# GDOv5_Board.net
KiCad netlist of a schematic drawn in EAGLE
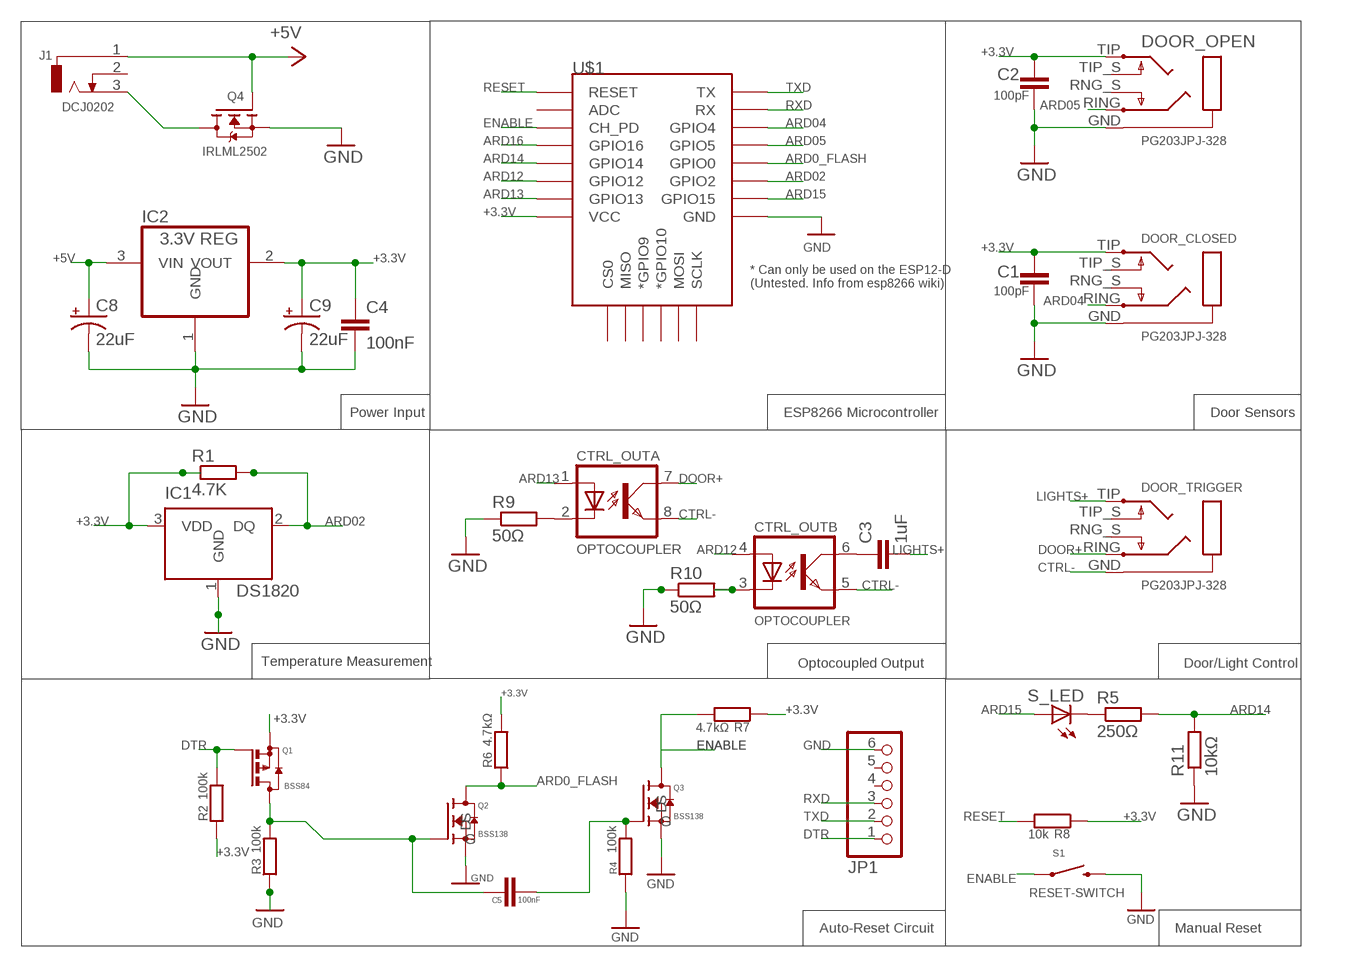
[diagram p0: schematic, sheet 1]

(export (version "E")
  (design (tool "Eeschema 10.0.6"))
  (components
    (comp (ref "C1")
      (value "100pF")
      (footprint "eagle-import:C1206")
      (libsource (lib "eagle-import") (part "C-EUC1206"))
    )
    (comp (ref "C2")
      (value "100pF")
      (footprint "eagle-import:C1206")
      (libsource (lib "eagle-import") (part "C-EUC1206"))
    )
    (comp (ref "C3")
      (value "1uF")
      (footprint "eagle-import:1206")
      (libsource (lib "eagle-import") (part "CAP1206"))
    )
    (comp (ref "C4")
      (value "100nF")
      (footprint "eagle-import:C1206")
      (libsource (lib "eagle-import") (part "C-EUC1206"))
    )
    (comp (ref "C5")
      (value "100nF")
      (footprint "eagle-import:C1206")
      (libsource (lib "eagle-import") (part "C-EUC1206"))
    )
    (comp (ref "C8")
      (value "22uF")
      (footprint "eagle-import:EIA3216")
      (libsource (lib "eagle-import") (part "10UF-TANT"))
    )
    (comp (ref "C9")
      (value "22uF")
      (footprint "eagle-import:EIA3216")
      (libsource (lib "eagle-import") (part "10UF-TANT"))
    )
    (comp (ref "CTRL_OUT")
      (value "OPTOCOUPLER")
      (footprint "eagle-import:DIL08")
      (libsource (lib "eagle-import") (part "ILD2"))
    )
    (comp (ref "DOOR_CLOSED")
      (value "PG203JPJ-328")
      (footprint "eagle-import:PG203J")
      (libsource (lib "eagle-import") (part "PG203JPJ-328"))
    )
    (comp (ref "DOOR_OPEN")
      (value "PG203JPJ-328")
      (footprint "eagle-import:PG203J")
      (libsource (lib "eagle-import") (part "PG203JPJ-328"))
    )
    (comp (ref "DOOR_TRIGGER")
      (value "PG203JPJ-328")
      (footprint "eagle-import:PG203J")
      (libsource (lib "eagle-import") (part "PG203JPJ-328"))
    )
    (comp (ref "IC1")
      (value "DS1820")
      (footprint "eagle-import:TO-92")
      (libsource (lib "eagle-import") (part "DS1820"))
    )
    (comp (ref "IC2")
      (value "3.3V REG")
      (footprint "eagle-import:SOT223")
      (fields (field (name "MPN") "REG1117"))
      (libsource (lib "eagle-import") (part "REG1117"))
    )
    (comp (ref "J1")
      (value "DCJ0202")
      (footprint "eagle-import:DCJ0202")
      (libsource (lib "eagle-import") (part "DCJ0202"))
    )
    (comp (ref "JP1")
      (value "PINHD-1X6")
      (footprint "eagle-import:1X06")
      (libsource (lib "eagle-import") (part "PINHD-1X6"))
    )
    (comp (ref "Q1")
      (value "BSS84")
      (footprint "eagle-import:SOT23")
      (libsource (lib "eagle-import") (part "BSS84"))
    )
    (comp (ref "Q2")
      (value "BSS138")
      (footprint "eagle-import:BSS138")
      (libsource (lib "eagle-import") (part "BSS138"))
    )
    (comp (ref "Q3")
      (value "BSS138")
      (footprint "eagle-import:BSS138")
      (libsource (lib "eagle-import") (part "BSS138"))
    )
    (comp (ref "Q4")
      (value "IRLML2502")
      (footprint "eagle-import:SOT23")
      (fields (field (name "MF") "Fairchild") (field (name "MPN") "BSS138"))
      (libsource (lib "eagle-import") (part "bss138_10_BSS138"))
    )
    (comp (ref "R1")
      (value "4.7K")
      (footprint "eagle-import:M3216")
      (libsource (lib "eagle-import") (part "R-EU_M3216"))
    )
    (comp (ref "R2")
      (value "100k")
      (footprint "eagle-import:M3216")
      (libsource (lib "eagle-import") (part "R-EU_M3216"))
    )
    (comp (ref "R3")
      (value "100k")
      (footprint "eagle-import:M3216")
      (libsource (lib "eagle-import") (part "R-EU_M3216"))
    )
    (comp (ref "R4")
      (value "100k")
      (footprint "eagle-import:M3216")
      (libsource (lib "eagle-import") (part "R-EU_M3216"))
    )
    (comp (ref "R5")
      (value "250Ω")
      (footprint "eagle-import:M3216")
      (libsource (lib "eagle-import") (part "R-EU_M3216"))
    )
    (comp (ref "R6")
      (value "4.7kΩ")
      (footprint "eagle-import:M3216")
      (libsource (lib "eagle-import") (part "R-EU_M3216"))
    )
    (comp (ref "R7")
      (value "4.7kΩ")
      (footprint "eagle-import:M3216")
      (libsource (lib "eagle-import") (part "R-EU_M3216"))
    )
    (comp (ref "R8")
      (value "10k")
      (footprint "eagle-import:M3216")
      (libsource (lib "eagle-import") (part "R-EU_M3216"))
    )
    (comp (ref "R9")
      (value "50Ω")
      (footprint "eagle-import:M3216")
      (libsource (lib "eagle-import") (part "R-EU_M3216"))
    )
    (comp (ref "R10")
      (value "50Ω")
      (footprint "eagle-import:M3216")
      (libsource (lib "eagle-import") (part "R-EU_M3216"))
    )
    (comp (ref "R11")
      (value "10kΩ")
      (footprint "eagle-import:M3216")
      (libsource (lib "eagle-import") (part "R-EU_M3216"))
    )
    (comp (ref "S1")
      (value "RESET-SWITCH")
      (footprint "eagle-import:TACTILE-SWITCH-1101NE")
      (libsource (lib "eagle-import") (part "SWITCH-MOMENTARY-2-SMD-1101NE"))
    )
    (comp (ref "S_LED")
      (value "LED5MM")
      (footprint "eagle-import:LED5MM")
      (libsource (lib "eagle-import") (part "LED5MM"))
    )
    (comp (ref "U$1")
      (value "ESP12ESMD")
      (footprint "eagle-import:ESP12E-SMD")
      (libsource (lib "eagle-import") (part "ESP12ESMD"))
    )
  )
  (nets
    (net (code "1") (name "+5V") (class "Default")
      (node (ref "C8") (pin "A") (pinfunction "+_A") (pintype "passive"))
      (node (ref "IC2") (pin "3") (pinfunction "VIN_3") (pintype "input"))
      (node (ref "J1") (pin "1") (pinfunction "1_1") (pintype "passive"))
      (node (ref "Q4") (pin "1") (pinfunction "G_1") (pintype "passive"))
    )
    (net (code "2") (name "/+3.3V") (class "Default")
      (node (ref "C1") (pin "1") (pinfunction "1_1") (pintype "passive"))
      (node (ref "C2") (pin "1") (pinfunction "1_1") (pintype "passive"))
      (node (ref "C4") (pin "1") (pinfunction "1_1") (pintype "passive"))
      (node (ref "C9") (pin "A") (pinfunction "+_A") (pintype "passive"))
      (node (ref "DOOR_CLOSED") (pin "TIP") (pinfunction "5_TIP") (pintype "passive"))
      (node (ref "DOOR_OPEN") (pin "TIP") (pinfunction "5_TIP") (pintype "passive"))
      (node (ref "IC1") (pin "3") (pinfunction "VDD_3") (pintype "input"))
      (node (ref "IC2") (pin "2") (pinfunction "VOUT_2") (pintype "output"))
      (node (ref "Q1") (pin "2") (pinfunction "S_2") (pintype "passive"))
      (node (ref "R1") (pin "1") (pinfunction "1_1") (pintype "passive"))
      (node (ref "R2") (pin "1") (pinfunction "1_1") (pintype "passive"))
      (node (ref "R6") (pin "2") (pinfunction "2_2") (pintype "passive"))
      (node (ref "R7") (pin "1") (pinfunction "1_1") (pintype "passive"))
      (node (ref "R8") (pin "1") (pinfunction "1_1") (pintype "passive"))
      (node (ref "U$1") (pin "VCC") (pinfunction "VCC_VCC") (pintype "bidirectional"))
    )
    (net (code "3") (name "/ARD0_FLASH") (class "Default")
      (node (ref "Q2") (pin "D") (pinfunction "D_D") (pintype "passive"))
      (node (ref "R6") (pin "1") (pinfunction "1_1") (pintype "passive"))
      (node (ref "U$1") (pin "GPIO0") (pinfunction "GPIO0_GPIO0") (pintype "bidirectional"))
    )
    (net (code "4") (name "/ARD02") (class "Default")
      (node (ref "IC1") (pin "2") (pinfunction "DQ_2") (pintype "output"))
      (node (ref "R1") (pin "2") (pinfunction "2_2") (pintype "passive"))
      (node (ref "U$1") (pin "GPIO2") (pinfunction "GPIO2_GPIO2") (pintype "bidirectional"))
    )
    (net (code "5") (name "/ARD04") (class "Default")
      (node (ref "DOOR_CLOSED") (pin "RING") (pinfunction "2_RING") (pintype "passive"))
      (node (ref "U$1") (pin "GPIO4") (pinfunction "GPIO4_GPIO4") (pintype "bidirectional"))
    )
    (net (code "6") (name "/ARD05") (class "Default")
      (node (ref "DOOR_OPEN") (pin "RING") (pinfunction "2_RING") (pintype "passive"))
      (node (ref "U$1") (pin "GPIO5") (pinfunction "GPIO5_GPIO5") (pintype "bidirectional"))
    )
    (net (code "7") (name "/ARD12") (class "Default")
      (node (ref "CTRL_OUT") (pin "4") (pinfunction "A_4") (pintype "passive"))
      (node (ref "U$1") (pin "GPIO12") (pinfunction "GPIO12_GPIO12") (pintype "bidirectional"))
    )
    (net (code "8") (name "/ARD13") (class "Default")
      (node (ref "CTRL_OUT") (pin "1") (pinfunction "A_1") (pintype "passive"))
      (node (ref "U$1") (pin "GPIO13") (pinfunction "GPIO13_GPIO13") (pintype "bidirectional"))
    )
    (net (code "9") (name "/ARD14") (class "Default")
      (node (ref "R11") (pin "2") (pinfunction "2_2") (pintype "passive"))
      (node (ref "R5") (pin "2") (pinfunction "2_2") (pintype "passive"))
      (node (ref "U$1") (pin "GPIO14") (pinfunction "GPIO14_GPIO14") (pintype "bidirectional"))
    )
    (net (code "10") (name "/ARD15") (class "Default")
      (node (ref "S_LED") (pin "A") (pinfunction "A_A") (pintype "passive"))
      (node (ref "U$1") (pin "GPIO15") (pinfunction "GPIO15_GPIO15") (pintype "bidirectional"))
    )
    (net (code "11") (name "/ARD16") (class "Default")
      (node (ref "U$1") (pin "GPIO16") (pinfunction "GPIO16_GPIO16") (pintype "bidirectional"))
    )
    (net (code "12") (name "/CTRL-") (class "Default")
      (node (ref "CTRL_OUT") (pin "5") (pinfunction "EMIT_5") (pintype "passive"))
      (node (ref "CTRL_OUT") (pin "8") (pinfunction "EMIT_8") (pintype "passive"))
      (node (ref "DOOR_TRIGGER") (pin "GND") (pinfunction "1_GND") (pintype "passive"))
    )
    (net (code "13") (name "/DOOR+") (class "Default")
      (node (ref "CTRL_OUT") (pin "7") (pinfunction "COL_7") (pintype "passive"))
      (node (ref "DOOR_TRIGGER") (pin "RING") (pinfunction "2_RING") (pintype "passive"))
    )
    (net (code "14") (name "/DTR") (class "Default")
      (node (ref "JP1") (pin "1") (pinfunction "1_1") (pintype "passive"))
      (node (ref "Q1") (pin "1") (pinfunction "G_1") (pintype "passive"))
      (node (ref "R2") (pin "2") (pinfunction "2_2") (pintype "passive"))
    )
    (net (code "15") (name "/ENABLE") (class "Default")
      (node (ref "Q3") (pin "D") (pinfunction "D_D") (pintype "passive"))
      (node (ref "R7") (pin "2") (pinfunction "2_2") (pintype "passive"))
      (node (ref "S1") (pin "P$1") (pinfunction "1_P$1") (pintype "passive"))
      (node (ref "U$1") (pin "CH_PD") (pinfunction "CH_PD_CH_PD") (pintype "bidirectional"))
    )
    (net (code "16") (name "/LIGHTS+") (class "Default")
      (node (ref "C3") (pin "2") (pinfunction "2_2") (pintype "passive"))
      (node (ref "DOOR_TRIGGER") (pin "TIP") (pinfunction "5_TIP") (pintype "passive"))
    )
    (net (code "17") (name "/RESET") (class "Default")
      (node (ref "R8") (pin "2") (pinfunction "2_2") (pintype "passive"))
      (node (ref "U$1") (pin "RESET") (pinfunction "RESET_RESET") (pintype "bidirectional"))
    )
    (net (code "18") (name "/RXD") (class "Default")
      (node (ref "JP1") (pin "3") (pinfunction "3_3") (pintype "passive"))
      (node (ref "U$1") (pin "RXD0") (pinfunction "RX_RXD0") (pintype "bidirectional"))
    )
    (net (code "19") (name "/TXD") (class "Default")
      (node (ref "JP1") (pin "2") (pinfunction "2_2") (pintype "passive"))
      (node (ref "U$1") (pin "TXD0") (pinfunction "TX_TXD0") (pintype "bidirectional"))
    )
    (net (code "20") (name "GND") (class "Default")
      (node (ref "C1") (pin "2") (pinfunction "2_2") (pintype "passive"))
      (node (ref "C2") (pin "2") (pinfunction "2_2") (pintype "passive"))
      (node (ref "C4") (pin "2") (pinfunction "2_2") (pintype "passive"))
      (node (ref "C8") (pin "C") (pinfunction "-_C") (pintype "passive"))
      (node (ref "C9") (pin "C") (pinfunction "-_C") (pintype "passive"))
      (node (ref "DOOR_CLOSED") (pin "GND") (pinfunction "1_GND") (pintype "passive"))
      (node (ref "DOOR_OPEN") (pin "GND") (pinfunction "1_GND") (pintype "passive"))
      (node (ref "IC1") (pin "1") (pinfunction "GND_1") (pintype "power_in"))
      (node (ref "IC2") (pin "1") (pinfunction "GND_1") (pintype "power_in"))
      (node (ref "JP1") (pin "6") (pinfunction "6_6") (pintype "passive"))
      (node (ref "Q2") (pin "S") (pinfunction "S_S") (pintype "passive"))
      (node (ref "Q3") (pin "S") (pinfunction "S_S") (pintype "passive"))
      (node (ref "Q4") (pin "2") (pinfunction "S_2") (pintype "passive"))
      (node (ref "R10") (pin "1") (pinfunction "1_1") (pintype "passive"))
      (node (ref "R11") (pin "1") (pinfunction "1_1") (pintype "passive"))
      (node (ref "R3") (pin "1") (pinfunction "1_1") (pintype "passive"))
      (node (ref "R4") (pin "1") (pinfunction "1_1") (pintype "passive"))
      (node (ref "R9") (pin "1") (pinfunction "1_1") (pintype "passive"))
      (node (ref "S1") (pin "P$2") (pinfunction "2_P$2") (pintype "passive"))
      (node (ref "U$1") (pin "GND") (pinfunction "GND_GND") (pintype "bidirectional"))
    )
    (net (code "21") (name "Net-(C5-Pad2)") (class "Default")
      (node (ref "C5") (pin "2") (pinfunction "2_2") (pintype "passive"))
      (node (ref "Q3") (pin "G") (pinfunction "G_G") (pintype "passive"))
      (node (ref "R4") (pin "2") (pinfunction "2_2") (pintype "passive"))
    )
    (net (code "22") (name "Net-(CTRL_OUTA-C)") (class "Default")
      (node (ref "CTRL_OUT") (pin "2") (pinfunction "C_2") (pintype "passive"))
      (node (ref "R9") (pin "2") (pinfunction "2_2") (pintype "passive"))
    )
    (net (code "23") (name "Net-(CTRL_OUTB-C)") (class "Default")
      (node (ref "CTRL_OUT") (pin "3") (pinfunction "C_3") (pintype "passive"))
      (node (ref "R10") (pin "2") (pinfunction "2_2") (pintype "passive"))
    )
    (net (code "24") (name "Net-(CTRL_OUTB-COL)") (class "Default")
      (node (ref "C3") (pin "1") (pinfunction "1_1") (pintype "passive"))
      (node (ref "CTRL_OUT") (pin "6") (pinfunction "COL_6") (pintype "passive"))
    )
    (net (code "25") (name "Net-(Q1-D)") (class "Default")
      (node (ref "C5") (pin "1") (pinfunction "1_1") (pintype "passive"))
      (node (ref "Q1") (pin "3") (pinfunction "D_3") (pintype "passive"))
      (node (ref "Q2") (pin "G") (pinfunction "G_G") (pintype "passive"))
      (node (ref "R3") (pin "2") (pinfunction "2_2") (pintype "passive"))
    )
    (net (code "26") (name "Net-(Q4-D)") (class "Default")
      (node (ref "J1") (pin "3") (pinfunction "3_3") (pintype "passive"))
      (node (ref "Q4") (pin "3") (pinfunction "D_3") (pintype "passive"))
    )
    (net (code "27") (name "Net-(S_LED-C)") (class "Default")
      (node (ref "R5") (pin "1") (pinfunction "1_1") (pintype "passive"))
      (node (ref "S_LED") (pin "K") (pinfunction "C_K") (pintype "passive"))
    )
    (net (code "28") (name "unconnected-(DOOR_CLOSED-3-PadRNG_S)") (class "Default")
      (node (ref "DOOR_CLOSED") (pin "RNG_S") (pinfunction "3_RNG_S") (pintype "passive"))
    )
    (net (code "29") (name "unconnected-(DOOR_CLOSED-4-PadTIP_S)") (class "Default")
      (node (ref "DOOR_CLOSED") (pin "TIP_S") (pinfunction "4_TIP_S") (pintype "passive"))
    )
    (net (code "30") (name "unconnected-(DOOR_OPEN-3-PadRNG_S)") (class "Default")
      (node (ref "DOOR_OPEN") (pin "RNG_S") (pinfunction "3_RNG_S") (pintype "passive"))
    )
    (net (code "31") (name "unconnected-(DOOR_OPEN-4-PadTIP_S)") (class "Default")
      (node (ref "DOOR_OPEN") (pin "TIP_S") (pinfunction "4_TIP_S") (pintype "passive"))
    )
    (net (code "32") (name "unconnected-(DOOR_TRIGGER-3-PadRNG_S)") (class "Default")
      (node (ref "DOOR_TRIGGER") (pin "RNG_S") (pinfunction "3_RNG_S") (pintype "passive"))
    )
    (net (code "33") (name "unconnected-(DOOR_TRIGGER-4-PadTIP_S)") (class "Default")
      (node (ref "DOOR_TRIGGER") (pin "TIP_S") (pinfunction "4_TIP_S") (pintype "passive"))
    )
    (net (code "34") (name "unconnected-(J1-Pad2)") (class "Default")
      (node (ref "J1") (pin "2") (pinfunction "2_2") (pintype "passive"))
    )
    (net (code "35") (name "unconnected-(JP1-Pad4)") (class "Default")
      (node (ref "JP1") (pin "4") (pinfunction "4_4") (pintype "passive"))
    )
    (net (code "36") (name "unconnected-(JP1-Pad5)") (class "Default")
      (node (ref "JP1") (pin "5") (pinfunction "5_5") (pintype "passive"))
    )
    (net (code "37") (name "unconnected-(U$1-*GPIO9-PadGPIO9)") (class "Default")
      (node (ref "U$1") (pin "GPIO9") (pinfunction "*GPIO9_GPIO9") (pintype "bidirectional"))
    )
    (net (code "38") (name "unconnected-(U$1-*GPIO10-PadGPIO10)") (class "Default")
      (node (ref "U$1") (pin "GPIO10") (pinfunction "*GPIO10_GPIO10") (pintype "bidirectional"))
    )
    (net (code "39") (name "unconnected-(U$1-PadADC)") (class "Default")
      (node (ref "U$1") (pin "ADC") (pinfunction "ADC_ADC") (pintype "bidirectional"))
    )
    (net (code "40") (name "unconnected-(U$1-PadCS0)") (class "Default")
      (node (ref "U$1") (pin "CS0") (pinfunction "CS0_CS0") (pintype "bidirectional"))
    )
    (net (code "41") (name "unconnected-(U$1-PadMISO)") (class "Default")
      (node (ref "U$1") (pin "MISO") (pinfunction "MISO_MISO") (pintype "bidirectional"))
    )
    (net (code "42") (name "unconnected-(U$1-PadMOSI)") (class "Default")
      (node (ref "U$1") (pin "MOSI") (pinfunction "MOSI_MOSI") (pintype "bidirectional"))
    )
    (net (code "43") (name "unconnected-(U$1-PadSCLK)") (class "Default")
      (node (ref "U$1") (pin "SCLK") (pinfunction "SCLK_SCLK") (pintype "bidirectional"))
    )
  )
)
